# PSPi.net
KiCad netlist of a schematic drawn in EAGLE
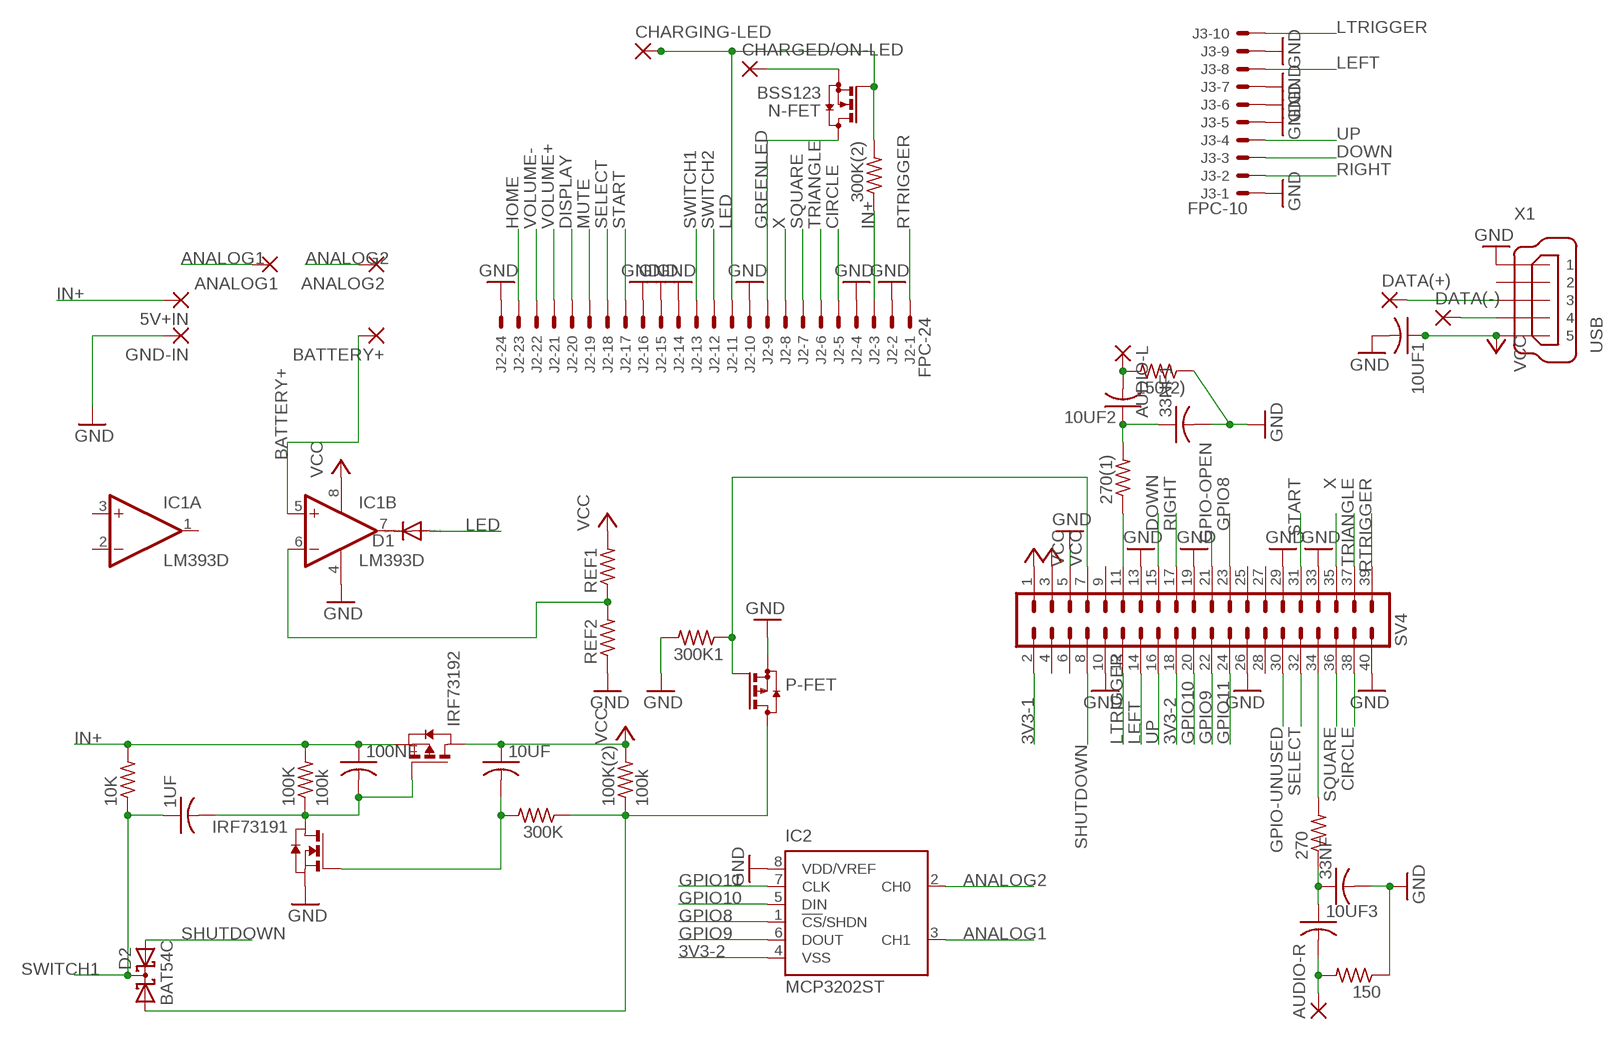
[diagram p0: schematic, sheet 1]

(export (version "E")
  (design (tool "Eeschema 10.0.6"))
  (components
    (comp (ref "1UF")
      (value "C-USC0805")
      (footprint "eagle-import:C0805")
      (libsource (lib "eagle-import") (part "C-USC0805"))
    )
    (comp (ref "5V+IN")
      (value "SMD2")
      (footprint "eagle-import:SMD1,27-2,54")
      (libsource (lib "eagle-import") (part "SMD2"))
    )
    (comp (ref "10K")
      (value "R-US_R0805")
      (footprint "eagle-import:R0805")
      (libsource (lib "eagle-import") (part "R-US_R0805"))
    )
    (comp (ref "10UF")
      (value "C-USC0805")
      (footprint "eagle-import:C0805")
      (libsource (lib "eagle-import") (part "C-USC0805"))
    )
    (comp (ref "10UF1")
      (value "C-USC0805")
      (footprint "eagle-import:C0805")
      (libsource (lib "eagle-import") (part "C-USC0805"))
    )
    (comp (ref "10UF2")
      (value "C-USC0805")
      (footprint "eagle-import:C0805")
      (libsource (lib "eagle-import") (part "C-USC0805"))
    )
    (comp (ref "10UF3")
      (value "C-USC0805")
      (footprint "eagle-import:C0805")
      (libsource (lib "eagle-import") (part "C-USC0805"))
    )
    (comp (ref "33NF")
      (value "C-USC0805")
      (footprint "eagle-import:C0805")
      (libsource (lib "eagle-import") (part "C-USC0805"))
    )
    (comp (ref "33NF1")
      (value "C-USC0805")
      (footprint "eagle-import:C0805")
      (libsource (lib "eagle-import") (part "C-USC0805"))
    )
    (comp (ref "100K")
      (value "100k")
      (footprint "eagle-import:R0805")
      (libsource (lib "eagle-import") (part "R-US_R0805"))
    )
    (comp (ref "100K(2)")
      (value "100k")
      (footprint "eagle-import:R0805")
      (libsource (lib "eagle-import") (part "R-US_R0805"))
    )
    (comp (ref "100NF")
      (value "C-USC0805")
      (footprint "eagle-import:C0805")
      (libsource (lib "eagle-import") (part "C-USC0805"))
    )
    (comp (ref "150")
      (value "R-US_R0805")
      (footprint "eagle-import:R0805")
      (libsource (lib "eagle-import") (part "R-US_R0805"))
    )
    (comp (ref "150(2)")
      (value "R-US_R0805")
      (footprint "eagle-import:R0805")
      (libsource (lib "eagle-import") (part "R-US_R0805"))
    )
    (comp (ref "270")
      (value "R-US_R0805")
      (footprint "eagle-import:R0805")
      (libsource (lib "eagle-import") (part "R-US_R0805"))
    )
    (comp (ref "270(1)")
      (value "R-US_R0805")
      (footprint "eagle-import:R0805")
      (libsource (lib "eagle-import") (part "R-US_R0805"))
    )
    (comp (ref "300K")
      (value "R-US_R0805")
      (footprint "eagle-import:R0805")
      (libsource (lib "eagle-import") (part "R-US_R0805"))
    )
    (comp (ref "300K(2)")
      (value "R-US_R0805")
      (footprint "eagle-import:R0805")
      (libsource (lib "eagle-import") (part "R-US_R0805"))
    )
    (comp (ref "300K1")
      (value "R-US_R0805")
      (footprint "eagle-import:R0805")
      (libsource (lib "eagle-import") (part "R-US_R0805"))
    )
    (comp (ref "ANALOG1")
      (value "SMD2")
      (footprint "eagle-import:SMD1,27-2,54")
      (libsource (lib "eagle-import") (part "SMD2"))
    )
    (comp (ref "ANALOG2")
      (value "SMD2")
      (footprint "eagle-import:SMD1,27-2,54")
      (libsource (lib "eagle-import") (part "SMD2"))
    )
    (comp (ref "AUDIO-L")
      (value "SMD2")
      (footprint "eagle-import:SMD1,27-2,54")
      (libsource (lib "eagle-import") (part "SMD2"))
    )
    (comp (ref "AUDIO-R")
      (value "SMD2")
      (footprint "eagle-import:SMD1,27-2,54")
      (libsource (lib "eagle-import") (part "SMD2"))
    )
    (comp (ref "BATTERY+")
      (value "SMD2")
      (footprint "eagle-import:SMD1,27-2,54")
      (libsource (lib "eagle-import") (part "SMD2"))
    )
    (comp (ref "CHARGED/ON-LED")
      (value "SMD2")
      (footprint "eagle-import:SMD1,27-2,54")
      (libsource (lib "eagle-import") (part "SMD2"))
    )
    (comp (ref "CHARGING-LED")
      (value "SMD2")
      (footprint "eagle-import:SMD1,27-2,54")
      (libsource (lib "eagle-import") (part "SMD2"))
    )
    (comp (ref "D1")
      (value "DIODE-SOD323-R")
      (footprint "eagle-import:SOD323-R")
      (libsource (lib "eagle-import") (part "DIODE-SOD323-R"))
    )
    (comp (ref "D2")
      (value "BAT54C")
      (footprint "eagle-import:SOT23")
      (libsource (lib "eagle-import") (part "BAT54C"))
    )
    (comp (ref "DATA(+)")
      (value "SMD2")
      (footprint "eagle-import:SMD1,27-2,54")
      (libsource (lib "eagle-import") (part "SMD2"))
    )
    (comp (ref "DATA(-)")
      (value "SMD2")
      (footprint "eagle-import:SMD1,27-2,54")
      (libsource (lib "eagle-import") (part "SMD2"))
    )
    (comp (ref "GND-IN")
      (value "SMD2")
      (footprint "eagle-import:SMD1,27-2,54")
      (libsource (lib "eagle-import") (part "SMD2"))
    )
    (comp (ref "IC1")
      (value "LM393D")
      (footprint "eagle-import:SO08")
      (libsource (lib "eagle-import") (part "LM393D"))
    )
    (comp (ref "IC2")
      (value "MCP3202ST")
      (footprint "eagle-import:TSSOP8")
      (fields (field (name "MF") "MICROCHIP") (field (name "MPN") "MCP3202-CI/ST"))
      (libsource (lib "eagle-import") (part "MCP3202ST"))
    )
    (comp (ref "IRF7319")
      (value "PN_MOSFET-SO8")
      (footprint "eagle-import:SO8")
      (libsource (lib "eagle-import") (part "PN_MOSFET-SO8"))
    )
    (comp (ref "J2")
      (value "FPC-24")
      (footprint "eagle-import:XF2R-2415-4A")
      (fields (field (name "MPN") "XF2R-2415-4A"))
      (libsource (lib "eagle-import") (part "XF2-24?15-4AR"))
    )
    (comp (ref "J3")
      (value "FPC-10")
      (footprint "eagle-import:XF2L-1035-1")
      (fields (field (name "MPN") "XF2L-1035-1A"))
      (libsource (lib "eagle-import") (part "XF2-10?35-1L"))
    )
    (comp (ref "N-FET")
      (value "BSS123")
      (footprint "eagle-import:SOT23")
      (libsource (lib "eagle-import") (part "BSS123"))
    )
    (comp (ref "P-FET")
      (value "BSS84")
      (footprint "eagle-import:SOT23")
      (libsource (lib "eagle-import") (part "BSS84"))
    )
    (comp (ref "REF1")
      (value "R-US_R0805")
      (footprint "eagle-import:R0805")
      (libsource (lib "eagle-import") (part "R-US_R0805"))
    )
    (comp (ref "REF2")
      (value "R-US_R0805")
      (footprint "eagle-import:R0805")
      (libsource (lib "eagle-import") (part "R-US_R0805"))
    )
    (comp (ref "SV4")
      (value "MA20-2")
      (footprint "eagle-import:MA20-2")
      (libsource (lib "eagle-import") (part "MA20-2"))
    )
    (comp (ref "X1")
      (value "USB")
      (footprint "eagle-import:32005-201")
      (libsource (lib "eagle-import") (part "MINI-USB-32005-201"))
    )
  )
  (nets
    (net (code "1") (name "/3V3-1") (class "Default")
      (node (ref "SV4") (pin "2") (pinfunction "2_2") (pintype "passive"))
    )
    (net (code "2") (name "/3V3-2") (class "Default")
      (node (ref "IC2") (pin "4") (pinfunction "VSS_4") (pintype "input"))
      (node (ref "SV4") (pin "18") (pinfunction "18_18") (pintype "passive"))
    )
    (net (code "3") (name "/ANALOG1") (class "Default")
      (node (ref "ANALOG1") (pin "1") (pinfunction "P_1") (pintype "passive"))
      (node (ref "IC2") (pin "3") (pinfunction "CH1_3") (pintype "input"))
    )
    (net (code "4") (name "/ANALOG2") (class "Default")
      (node (ref "ANALOG2") (pin "1") (pinfunction "P_1") (pintype "passive"))
      (node (ref "IC2") (pin "2") (pinfunction "CH0_2") (pintype "input"))
    )
    (net (code "5") (name "/BATTERY+") (class "Default")
      (node (ref "BATTERY+") (pin "1") (pinfunction "P_1") (pintype "passive"))
      (node (ref "IC1") (pin "5") (pinfunction "+IN_5") (pintype "input"))
    )
    (net (code "6") (name "/CIRCLE") (class "Default")
      (node (ref "J2") (pin "5") (pinfunction "MS_5") (pintype "passive"))
      (node (ref "SV4") (pin "38") (pinfunction "38_38") (pintype "passive"))
    )
    (net (code "7") (name "/DISPLAY") (class "Default")
      (node (ref "J2") (pin "20") (pinfunction "MS_20") (pintype "passive"))
    )
    (net (code "8") (name "/DOWN") (class "Default")
      (node (ref "J3") (pin "3") (pinfunction "MS_3") (pintype "passive"))
      (node (ref "SV4") (pin "15") (pinfunction "15_15") (pintype "passive"))
    )
    (net (code "9") (name "/GPIO-OPEN") (class "Default")
      (node (ref "SV4") (pin "21") (pinfunction "21_21") (pintype "passive"))
    )
    (net (code "10") (name "/GPIO-UNUSED") (class "Default")
      (node (ref "SV4") (pin "30") (pinfunction "30_30") (pintype "passive"))
    )
    (net (code "11") (name "/GPIO8") (class "Default")
      (node (ref "IC2") (pin "1") (pinfunction "~{CS}/SHDN_1") (pintype "input"))
      (node (ref "SV4") (pin "23") (pinfunction "23_23") (pintype "passive"))
    )
    (net (code "12") (name "/GPIO9") (class "Default")
      (node (ref "IC2") (pin "6") (pinfunction "DOUT_6") (pintype "input"))
      (node (ref "SV4") (pin "22") (pinfunction "22_22") (pintype "passive"))
    )
    (net (code "13") (name "/GPIO10") (class "Default")
      (node (ref "IC2") (pin "5") (pinfunction "DIN_5") (pintype "input"))
      (node (ref "SV4") (pin "20") (pinfunction "20_20") (pintype "passive"))
    )
    (net (code "14") (name "/GPIO11") (class "Default")
      (node (ref "IC2") (pin "7") (pinfunction "CLK_7") (pintype "input"))
      (node (ref "SV4") (pin "24") (pinfunction "24_24") (pintype "passive"))
    )
    (net (code "15") (name "/GREENLED") (class "Default")
      (node (ref "J2") (pin "9") (pinfunction "MS_9") (pintype "passive"))
      (node (ref "N-FET") (pin "3") (pinfunction "D_3") (pintype "passive"))
    )
    (net (code "16") (name "/HOME") (class "Default")
      (node (ref "J2") (pin "23") (pinfunction "MS_23") (pintype "passive"))
    )
    (net (code "17") (name "/IN+") (class "Default")
      (node (ref "100K") (pin "2") (pinfunction "2_2") (pintype "passive"))
      (node (ref "100NF") (pin "1") (pinfunction "1_1") (pintype "passive"))
      (node (ref "10K") (pin "2") (pinfunction "2_2") (pintype "passive"))
      (node (ref "300K(2)") (pin "1") (pinfunction "1_1") (pintype "passive"))
      (node (ref "5V+IN") (pin "1") (pinfunction "P_1") (pintype "passive"))
      (node (ref "IRF7319") (pin "3") (pinfunction "S_3") (pintype "passive"))
      (node (ref "J2") (pin "3") (pinfunction "MS_3") (pintype "passive"))
    )
    (net (code "18") (name "/LED") (class "Default")
      (node (ref "300K(2)") (pin "2") (pinfunction "2_2") (pintype "passive"))
      (node (ref "CHARGING-LED") (pin "1") (pinfunction "P_1") (pintype "passive"))
      (node (ref "D1") (pin "A") (pinfunction "A_A") (pintype "passive"))
      (node (ref "J2") (pin "11") (pinfunction "MS_11") (pintype "passive"))
      (node (ref "N-FET") (pin "1") (pinfunction "G_1") (pintype "passive"))
    )
    (net (code "19") (name "/LEFT") (class "Default")
      (node (ref "J3") (pin "8") (pinfunction "MS_8") (pintype "passive"))
      (node (ref "SV4") (pin "14") (pinfunction "14_14") (pintype "passive"))
    )
    (net (code "20") (name "/LTRIGGER") (class "Default")
      (node (ref "J3") (pin "10") (pinfunction "MS_10") (pintype "passive"))
      (node (ref "SV4") (pin "12") (pinfunction "12_12") (pintype "passive"))
    )
    (net (code "21") (name "/MUTE") (class "Default")
      (node (ref "J2") (pin "19") (pinfunction "MS_19") (pintype "passive"))
    )
    (net (code "22") (name "/RIGHT") (class "Default")
      (node (ref "J3") (pin "2") (pinfunction "MS_2") (pintype "passive"))
      (node (ref "SV4") (pin "17") (pinfunction "17_17") (pintype "passive"))
    )
    (net (code "23") (name "/RTRIGGER") (class "Default")
      (node (ref "J2") (pin "1") (pinfunction "MSV_1") (pintype "passive"))
      (node (ref "SV4") (pin "39") (pinfunction "39_39") (pintype "passive"))
    )
    (net (code "24") (name "/SELECT") (class "Default")
      (node (ref "J2") (pin "18") (pinfunction "MS_18") (pintype "passive"))
      (node (ref "SV4") (pin "32") (pinfunction "32_32") (pintype "passive"))
    )
    (net (code "25") (name "/SHUTDOWN") (class "Default")
      (node (ref "D2") (pin "2") (pinfunction "A2_2") (pintype "passive"))
      (node (ref "SV4") (pin "8") (pinfunction "8_8") (pintype "passive"))
    )
    (net (code "26") (name "/SQUARE") (class "Default")
      (node (ref "J2") (pin "7") (pinfunction "MS_7") (pintype "passive"))
      (node (ref "SV4") (pin "36") (pinfunction "36_36") (pintype "passive"))
    )
    (net (code "27") (name "/START") (class "Default")
      (node (ref "J2") (pin "17") (pinfunction "MS_17") (pintype "passive"))
      (node (ref "SV4") (pin "31") (pinfunction "31_31") (pintype "passive"))
    )
    (net (code "28") (name "/SWITCH1") (class "Default")
      (node (ref "10K") (pin "1") (pinfunction "1_1") (pintype "passive"))
      (node (ref "1UF") (pin "1") (pinfunction "1_1") (pintype "passive"))
      (node (ref "D2") (pin "3") (pinfunction "CC_3") (pintype "passive"))
      (node (ref "J2") (pin "13") (pinfunction "MS_13") (pintype "passive"))
    )
    (net (code "29") (name "/SWITCH2") (class "Default")
      (node (ref "J2") (pin "12") (pinfunction "MS_12") (pintype "passive"))
    )
    (net (code "30") (name "/TRIANGLE") (class "Default")
      (node (ref "J2") (pin "6") (pinfunction "MS_6") (pintype "passive"))
      (node (ref "SV4") (pin "37") (pinfunction "37_37") (pintype "passive"))
    )
    (net (code "31") (name "/UP") (class "Default")
      (node (ref "J3") (pin "4") (pinfunction "MS_4") (pintype "passive"))
      (node (ref "SV4") (pin "16") (pinfunction "16_16") (pintype "passive"))
    )
    (net (code "32") (name "/VOLUME+") (class "Default")
      (node (ref "J2") (pin "21") (pinfunction "MS_21") (pintype "passive"))
    )
    (net (code "33") (name "/VOLUME-") (class "Default")
      (node (ref "J2") (pin "22") (pinfunction "MS_22") (pintype "passive"))
    )
    (net (code "34") (name "/X") (class "Default")
      (node (ref "J2") (pin "8") (pinfunction "MS_8") (pintype "passive"))
      (node (ref "SV4") (pin "35") (pinfunction "35_35") (pintype "passive"))
    )
    (net (code "35") (name "GND") (class "Default")
      (node (ref "10UF1") (pin "2") (pinfunction "2_2") (pintype "passive"))
      (node (ref "150") (pin "1") (pinfunction "1_1") (pintype "passive"))
      (node (ref "150(2)") (pin "1") (pinfunction "1_1") (pintype "passive"))
      (node (ref "300K1") (pin "2") (pinfunction "2_2") (pintype "passive"))
      (node (ref "33NF") (pin "2") (pinfunction "2_2") (pintype "passive"))
      (node (ref "33NF1") (pin "2") (pinfunction "2_2") (pintype "passive"))
      (node (ref "GND-IN") (pin "1") (pinfunction "P_1") (pintype "passive"))
      (node (ref "IC1") (pin "4") (pinfunction "V-_4") (pintype "power_in"))
      (node (ref "IC2") (pin "8") (pinfunction "VDD/VREF_8") (pintype "input"))
      (node (ref "IRF7319") (pin "1") (pinfunction "S_1") (pintype "passive"))
      (node (ref "J2") (pin "10") (pinfunction "MS_10") (pintype "passive"))
      (node (ref "J2") (pin "14") (pinfunction "MS_14") (pintype "passive"))
      (node (ref "J2") (pin "15") (pinfunction "MS_15") (pintype "passive"))
      (node (ref "J2") (pin "16") (pinfunction "MS_16") (pintype "passive"))
      (node (ref "J2") (pin "2") (pinfunction "MS_2") (pintype "passive"))
      (node (ref "J2") (pin "24") (pinfunction "MS_24") (pintype "passive"))
      (node (ref "J2") (pin "4") (pinfunction "MS_4") (pintype "passive"))
      (node (ref "J3") (pin "1") (pinfunction "MSV_1") (pintype "passive"))
      (node (ref "J3") (pin "5") (pinfunction "MS_5") (pintype "passive"))
      (node (ref "J3") (pin "6") (pinfunction "MS_6") (pintype "passive"))
      (node (ref "J3") (pin "7") (pinfunction "MS_7") (pintype "passive"))
      (node (ref "J3") (pin "9") (pinfunction "MS_9") (pintype "passive"))
      (node (ref "P-FET") (pin "2") (pinfunction "S_2") (pintype "passive"))
      (node (ref "REF2") (pin "1") (pinfunction "1_1") (pintype "passive"))
      (node (ref "SV4") (pin "10") (pinfunction "10_10") (pintype "passive"))
      (node (ref "SV4") (pin "13") (pinfunction "13_13") (pintype "passive"))
      (node (ref "SV4") (pin "19") (pinfunction "19_19") (pintype "passive"))
      (node (ref "SV4") (pin "26") (pinfunction "26_26") (pintype "passive"))
      (node (ref "SV4") (pin "29") (pinfunction "29_29") (pintype "passive"))
      (node (ref "SV4") (pin "33") (pinfunction "33_33") (pintype "passive"))
      (node (ref "SV4") (pin "40") (pinfunction "40_40") (pintype "passive"))
      (node (ref "SV4") (pin "5") (pinfunction "5_5") (pintype "passive"))
      (node (ref "X1") (pin "1") (pinfunction "1_1") (pintype "passive"))
    )
    (net (code "36") (name "Net-(10UF2-Pad1)") (class "Default")
      (node (ref "10UF2") (pin "1") (pinfunction "1_1") (pintype "passive"))
      (node (ref "270(1)") (pin "2") (pinfunction "2_2") (pintype "passive"))
      (node (ref "33NF1") (pin "1") (pinfunction "1_1") (pintype "passive"))
    )
    (net (code "37") (name "Net-(10UF3-Pad1)") (class "Default")
      (node (ref "10UF3") (pin "1") (pinfunction "1_1") (pintype "passive"))
      (node (ref "270") (pin "1") (pinfunction "1_1") (pintype "passive"))
      (node (ref "33NF") (pin "1") (pinfunction "1_1") (pintype "passive"))
    )
    (net (code "38") (name "Net-(270(1)-Pad1)") (class "Default")
      (node (ref "270(1)") (pin "1") (pinfunction "1_1") (pintype "passive"))
      (node (ref "SV4") (pin "11") (pinfunction "11_11") (pintype "passive"))
    )
    (net (code "39") (name "Net-(270-Pad2)") (class "Default")
      (node (ref "270") (pin "2") (pinfunction "2_2") (pintype "passive"))
      (node (ref "SV4") (pin "34") (pinfunction "34_34") (pintype "passive"))
    )
    (net (code "40") (name "Net-(AUDIO-L-P)") (class "Default")
      (node (ref "10UF2") (pin "2") (pinfunction "2_2") (pintype "passive"))
      (node (ref "150(2)") (pin "2") (pinfunction "2_2") (pintype "passive"))
      (node (ref "AUDIO-L") (pin "1") (pinfunction "P_1") (pintype "passive"))
    )
    (net (code "41") (name "Net-(AUDIO-R-P)") (class "Default")
      (node (ref "10UF3") (pin "2") (pinfunction "2_2") (pintype "passive"))
      (node (ref "150") (pin "2") (pinfunction "2_2") (pintype "passive"))
      (node (ref "AUDIO-R") (pin "1") (pinfunction "P_1") (pintype "passive"))
    )
    (net (code "42") (name "Net-(CHARGED/ON-LED-P)") (class "Default")
      (node (ref "CHARGED/ON-LED") (pin "1") (pinfunction "P_1") (pintype "passive"))
      (node (ref "N-FET") (pin "2") (pinfunction "S_2") (pintype "passive"))
    )
    (net (code "43") (name "Net-(D2-A1)") (class "Default")
      (node (ref "100K(2)") (pin "1") (pinfunction "1_1") (pintype "passive"))
      (node (ref "300K") (pin "1") (pinfunction "1_1") (pintype "passive"))
      (node (ref "D2") (pin "1") (pinfunction "A1_1") (pintype "passive"))
      (node (ref "P-FET") (pin "3") (pinfunction "D_3") (pintype "passive"))
    )
    (net (code "44") (name "Net-(DATA(+)-P)") (class "Default")
      (node (ref "DATA(+)") (pin "1") (pinfunction "P_1") (pintype "passive"))
      (node (ref "X1") (pin "3") (pinfunction "3_3") (pintype "passive"))
    )
    (net (code "45") (name "Net-(DATA(-)-P)") (class "Default")
      (node (ref "DATA(-)") (pin "1") (pinfunction "P_1") (pintype "passive"))
      (node (ref "X1") (pin "4") (pinfunction "4_4") (pintype "passive"))
    )
    (net (code "46") (name "Net-(IC1B--IN)") (class "Default")
      (node (ref "IC1") (pin "6") (pinfunction "-IN_6") (pintype "input"))
      (node (ref "REF1") (pin "1") (pinfunction "1_1") (pintype "passive"))
      (node (ref "REF2") (pin "2") (pinfunction "2_2") (pintype "passive"))
    )
    (net (code "47") (name "Net-(IC1B-OUT)") (class "Default")
      (node (ref "D1") (pin "C") (pinfunction "C_C") (pintype "passive"))
      (node (ref "IC1") (pin "7") (pinfunction "OUT_7") (pintype "output"))
    )
    (net (code "48") (name "Net-(IRF7319A-G)") (class "Default")
      (node (ref "10UF") (pin "2") (pinfunction "2_2") (pintype "passive"))
      (node (ref "300K") (pin "2") (pinfunction "2_2") (pintype "passive"))
      (node (ref "IRF7319") (pin "2") (pinfunction "G_2") (pintype "passive"))
    )
    (net (code "49") (name "Net-(IRF7319B-G)") (class "Default")
      (node (ref "100K") (pin "1") (pinfunction "1_1") (pintype "passive"))
      (node (ref "100NF") (pin "2") (pinfunction "2_2") (pintype "passive"))
      (node (ref "1UF") (pin "2") (pinfunction "2_2") (pintype "passive"))
      (node (ref "IRF7319") (pin "4") (pinfunction "G_4") (pintype "passive"))
      (node (ref "IRF7319") (pin "7") (pinfunction "D_7") (pintype "passive"))
      (node (ref "IRF7319") (pin "8") (pinfunction "D_8") (pintype "passive"))
    )
    (net (code "50") (name "Net-(P-FET-G)") (class "Default")
      (node (ref "300K1") (pin "1") (pinfunction "1_1") (pintype "passive"))
      (node (ref "P-FET") (pin "1") (pinfunction "G_1") (pintype "passive"))
      (node (ref "SV4") (pin "7") (pinfunction "7_7") (pintype "passive"))
    )
    (net (code "51") (name "VCC") (class "Default")
      (node (ref "100K(2)") (pin "2") (pinfunction "2_2") (pintype "passive"))
      (node (ref "10UF") (pin "1") (pinfunction "1_1") (pintype "passive"))
      (node (ref "10UF1") (pin "1") (pinfunction "1_1") (pintype "passive"))
      (node (ref "IC1") (pin "8") (pinfunction "V+_8") (pintype "power_in"))
      (node (ref "IRF7319") (pin "5") (pinfunction "D_5") (pintype "passive"))
      (node (ref "IRF7319") (pin "6") (pinfunction "D_6") (pintype "passive"))
      (node (ref "REF1") (pin "2") (pinfunction "2_2") (pintype "passive"))
      (node (ref "SV4") (pin "1") (pinfunction "1_1") (pintype "passive"))
      (node (ref "SV4") (pin "3") (pinfunction "3_3") (pintype "passive"))
      (node (ref "X1") (pin "5") (pinfunction "5_5") (pintype "passive"))
    )
    (net (code "52") (name "unconnected-(IC1A-+IN-Pad3)") (class "Default")
      (node (ref "IC1") (pin "3") (pinfunction "+IN_3") (pintype "input"))
    )
    (net (code "53") (name "unconnected-(IC1A--IN-Pad2)") (class "Default")
      (node (ref "IC1") (pin "2") (pinfunction "-IN_2") (pintype "input"))
    )
    (net (code "54") (name "unconnected-(IC1A-OUT-Pad1)") (class "Default")
      (node (ref "IC1") (pin "1") (pinfunction "OUT_1") (pintype "output"))
    )
    (net (code "55") (name "unconnected-(SV4-Pad4)") (class "Default")
      (node (ref "SV4") (pin "4") (pinfunction "4_4") (pintype "passive"))
    )
    (net (code "56") (name "unconnected-(SV4-Pad6)") (class "Default")
      (node (ref "SV4") (pin "6") (pinfunction "6_6") (pintype "passive"))
    )
    (net (code "57") (name "unconnected-(SV4-Pad9)") (class "Default")
      (node (ref "SV4") (pin "9") (pinfunction "9_9") (pintype "passive"))
    )
    (net (code "58") (name "unconnected-(SV4-Pad25)") (class "Default")
      (node (ref "SV4") (pin "25") (pinfunction "25_25") (pintype "passive"))
    )
    (net (code "59") (name "unconnected-(SV4-Pad27)") (class "Default")
      (node (ref "SV4") (pin "27") (pinfunction "27_27") (pintype "passive"))
    )
    (net (code "60") (name "unconnected-(SV4-Pad28)") (class "Default")
      (node (ref "SV4") (pin "28") (pinfunction "28_28") (pintype "passive"))
    )
    (net (code "61") (name "unconnected-(X1-Pad2)") (class "Default")
      (node (ref "X1") (pin "2") (pinfunction "2_2") (pintype "passive"))
    )
  )
)
